# TIA.net
KiCad netlist of a schematic drawn in Altium Designer
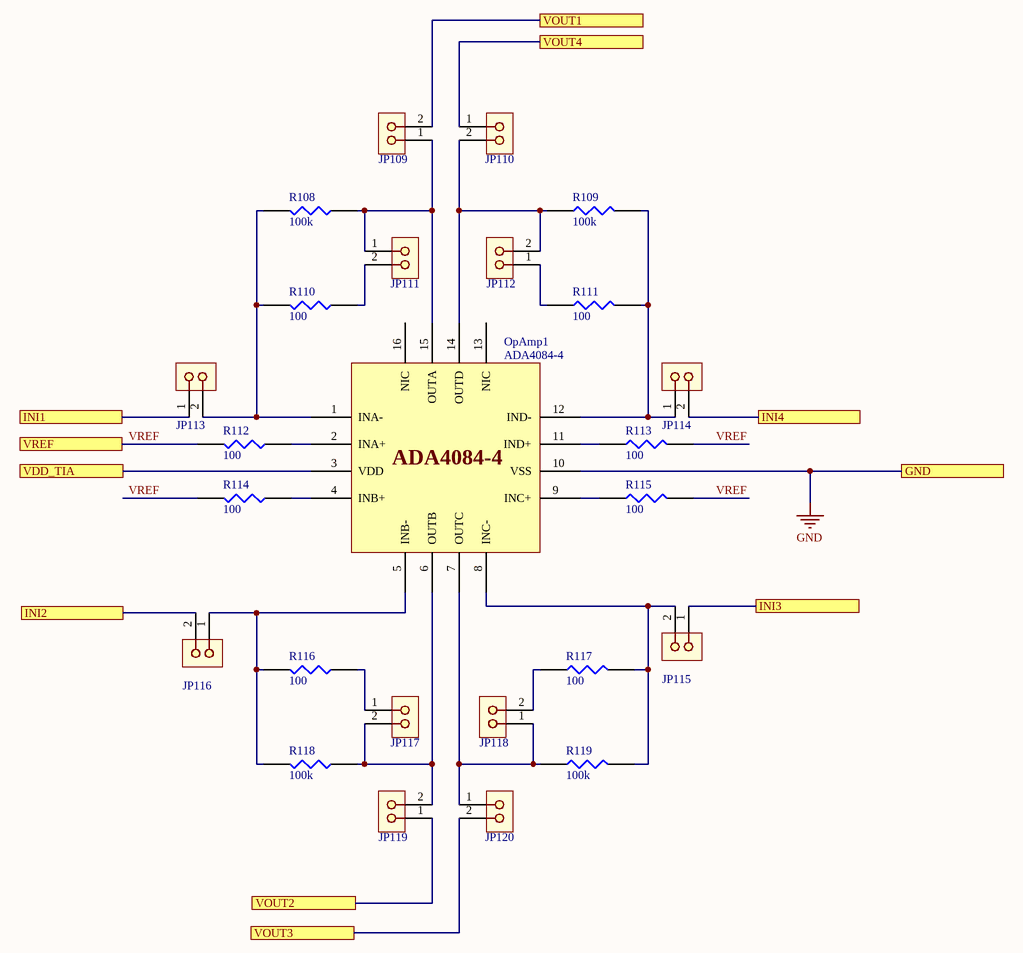
[diagram p0: TIA.SchDoc]

(export (version "E")
  (design (tool "Eeschema 10.0.6"))
  (components
    (comp (ref "JP109")
      (value "01x02")
      (footprint "01x02_0.1in_th_straight_b_nom")
      (description "01X02 generic terminal connector")
      (libsource (lib "") (part "01x02_2"))
    )
    (comp (ref "JP110")
      (value "01x02")
      (footprint "01x02_0.1in_th_straight_b_nom")
      (description "01X02 generic terminal connector")
      (libsource (lib "") (part "01x02_1"))
    )
    (comp (ref "JP111")
      (value "01x02")
      (footprint "01x02_0.1in_th_straight_b_nom")
      (description "01X02 generic terminal connector")
      (libsource (lib "") (part "01x02_1"))
    )
    (comp (ref "JP112")
      (value "01x02")
      (footprint "01x02_0.1in_th_straight_b_nom")
      (description "01X02 generic terminal connector")
      (libsource (lib "") (part "01x02_2"))
    )
    (comp (ref "JP113")
      (value "01x02")
      (footprint "01x02_0.1in_th_straight_b_nom")
      (description "01X02 generic terminal connector")
      (libsource (lib "") (part "01x02_3"))
    )
    (comp (ref "JP114")
      (value "01x02")
      (footprint "01x02_0.1in_th_straight_b_nom")
      (description "01X02 generic terminal connector")
      (libsource (lib "") (part "01x02_3"))
    )
    (comp (ref "JP115")
      (value "01x02")
      (footprint "01x02_0.1in_th_straight_b_nom")
      (description "01X02 generic terminal connector")
      (libsource (lib "Chip1_TestBoard") (part "01x02"))
    )
    (comp (ref "JP116")
      (value "01x02")
      (footprint "01x02_0.1in_th_straight_b_nom")
      (description "01X02 generic terminal connector")
      (libsource (lib "Chip1_TestBoard") (part "01x02"))
    )
    (comp (ref "JP117")
      (value "01x02")
      (footprint "01x02_0.1in_th_straight_b_nom")
      (description "01X02 generic terminal connector")
      (libsource (lib "") (part "01x02_1"))
    )
    (comp (ref "JP118")
      (value "01x02")
      (footprint "01x02_0.1in_th_straight_b_nom")
      (description "01X02 generic terminal connector")
      (libsource (lib "") (part "01x02_2"))
    )
    (comp (ref "JP119")
      (value "01x02")
      (footprint "01x02_0.1in_th_straight_b_nom")
      (description "01X02 generic terminal connector")
      (libsource (lib "") (part "01x02_2"))
    )
    (comp (ref "JP120")
      (value "01x02")
      (footprint "01x02_0.1in_th_straight_b_nom")
      (description "01X02 generic terminal connector")
      (libsource (lib "") (part "01x02_1"))
    )
    (comp (ref "OpAmp1")
      (value "ADA4084-4")
      (footprint "ADA4084-4")
      (description "Quad Ultra-Precision Op Amps")
      (libsource (lib "ICXTRAP1") (part "ADA4084-4"))
    )
    (comp (ref "R108")
      (value "100k")
      (footprint "R0805")
      (libsource (lib "Chip1_TestBoard") (part "Res 100k"))
    )
    (comp (ref "R109")
      (value "100k")
      (footprint "R0805")
      (libsource (lib "Chip1_TestBoard") (part "Res 100k"))
    )
    (comp (ref "R110") (value "100") (footprint "R0805") (libsource (lib "Chip1_TestBoard") (part "Res 100")))
    (comp (ref "R111") (value "100") (footprint "R0805") (libsource (lib "Chip1_TestBoard") (part "Res 100")))
    (comp (ref "R112") (value "100") (footprint "R0805") (libsource (lib "Chip1_TestBoard") (part "Res 100")))
    (comp (ref "R113") (value "100") (footprint "R0805") (libsource (lib "Chip1_TestBoard") (part "Res 100")))
    (comp (ref "R114") (value "100") (footprint "R0805") (libsource (lib "Chip1_TestBoard") (part "Res 100")))
    (comp (ref "R115") (value "100") (footprint "R0805") (libsource (lib "Chip1_TestBoard") (part "Res 100")))
    (comp (ref "R116") (value "100") (footprint "R0805") (libsource (lib "Chip1_TestBoard") (part "Res 100")))
    (comp (ref "R117") (value "100") (footprint "R0805") (libsource (lib "Chip1_TestBoard") (part "Res 100")))
    (comp (ref "R118")
      (value "100k")
      (footprint "R0805")
      (libsource (lib "Chip1_TestBoard") (part "Res 100k"))
    )
    (comp (ref "R119")
      (value "100k")
      (footprint "R0805")
      (libsource (lib "Chip1_TestBoard") (part "Res 100k"))
    )
  )
  (nets
    (net (code "1") (name "/INI1") (class "Default")
      (node (ref "JP113") (pin "1") (pinfunction "1_1") (pintype "passive"))
    )
    (net (code "2") (name "/INI2") (class "Default")
      (node (ref "JP116") (pin "2") (pinfunction "2_2") (pintype "passive"))
    )
    (net (code "3") (name "/INI3") (class "Default")
      (node (ref "JP115") (pin "1") (pinfunction "1_1") (pintype "passive"))
    )
    (net (code "4") (name "/INI4") (class "Default")
      (node (ref "JP114") (pin "2") (pinfunction "2_2") (pintype "passive"))
    )
    (net (code "5") (name "/VDD_TIA") (class "Default")
      (node (ref "OpAmp1") (pin "3") (pinfunction "VDD_3") (pintype "passive"))
    )
    (net (code "6") (name "/VOUT1") (class "Default")
      (node (ref "JP109") (pin "2") (pinfunction "2_2") (pintype "passive"))
    )
    (net (code "7") (name "/VOUT2") (class "Default")
      (node (ref "JP119") (pin "1") (pinfunction "1_1") (pintype "passive"))
    )
    (net (code "8") (name "/VOUT3") (class "Default")
      (node (ref "JP120") (pin "2") (pinfunction "2_2") (pintype "passive"))
    )
    (net (code "9") (name "/VOUT4") (class "Default")
      (node (ref "JP110") (pin "1") (pinfunction "1_1") (pintype "passive"))
    )
    (net (code "10") (name "/VREF") (class "Default")
      (node (ref "R112") (pin "2") (pinfunction "2_2") (pintype "passive"))
      (node (ref "R113") (pin "2") (pinfunction "2_2") (pintype "passive"))
      (node (ref "R114") (pin "2") (pinfunction "2_2") (pintype "passive"))
      (node (ref "R115") (pin "2") (pinfunction "2_2") (pintype "passive"))
    )
    (net (code "11") (name "GND") (class "Default")
      (node (ref "OpAmp1") (pin "10") (pinfunction "VSS_10") (pintype "passive"))
    )
    (net (code "12") (name "Net-(JP111-Pad2)") (class "Default")
      (node (ref "JP111") (pin "2") (pinfunction "2_2") (pintype "passive"))
      (node (ref "R110") (pin "1") (pinfunction "1_1") (pintype "passive"))
    )
    (net (code "13") (name "Net-(JP112-Pad1)") (class "Default")
      (node (ref "JP112") (pin "1") (pinfunction "1_1") (pintype "passive"))
      (node (ref "R111") (pin "1") (pinfunction "1_1") (pintype "passive"))
    )
    (net (code "14") (name "Net-(JP117-Pad1)") (class "Default")
      (node (ref "JP117") (pin "1") (pinfunction "1_1") (pintype "passive"))
      (node (ref "R116") (pin "1") (pinfunction "1_1") (pintype "passive"))
    )
    (net (code "15") (name "Net-(JP118-Pad2)") (class "Default")
      (node (ref "JP118") (pin "2") (pinfunction "2_2") (pintype "passive"))
      (node (ref "R117") (pin "1") (pinfunction "1_1") (pintype "passive"))
    )
    (net (code "16") (name "Net-(OpAmp1-INA+)") (class "Default")
      (node (ref "OpAmp1") (pin "2") (pinfunction "INA+_2") (pintype "passive"))
      (node (ref "R112") (pin "1") (pinfunction "1_1") (pintype "passive"))
    )
    (net (code "17") (name "Net-(OpAmp1-INA-)") (class "Default")
      (node (ref "JP113") (pin "2") (pinfunction "2_2") (pintype "passive"))
      (node (ref "OpAmp1") (pin "1") (pinfunction "INA-_1") (pintype "passive"))
      (node (ref "R108") (pin "2") (pinfunction "2_2") (pintype "passive"))
      (node (ref "R110") (pin "2") (pinfunction "2_2") (pintype "passive"))
    )
    (net (code "18") (name "Net-(OpAmp1-INB+)") (class "Default")
      (node (ref "OpAmp1") (pin "4") (pinfunction "INB+_4") (pintype "passive"))
      (node (ref "R114") (pin "1") (pinfunction "1_1") (pintype "passive"))
    )
    (net (code "19") (name "Net-(OpAmp1-INB-)") (class "Default")
      (node (ref "JP116") (pin "1") (pinfunction "1_1") (pintype "passive"))
      (node (ref "OpAmp1") (pin "5") (pinfunction "INB-_5") (pintype "passive"))
      (node (ref "R116") (pin "2") (pinfunction "2_2") (pintype "passive"))
      (node (ref "R118") (pin "2") (pinfunction "2_2") (pintype "passive"))
    )
    (net (code "20") (name "Net-(OpAmp1-INC+)") (class "Default")
      (node (ref "OpAmp1") (pin "9") (pinfunction "INC+_9") (pintype "passive"))
      (node (ref "R115") (pin "1") (pinfunction "1_1") (pintype "passive"))
    )
    (net (code "21") (name "Net-(OpAmp1-INC-)") (class "Default")
      (node (ref "JP115") (pin "2") (pinfunction "2_2") (pintype "passive"))
      (node (ref "OpAmp1") (pin "8") (pinfunction "INC-_8") (pintype "passive"))
      (node (ref "R117") (pin "2") (pinfunction "2_2") (pintype "passive"))
      (node (ref "R119") (pin "2") (pinfunction "2_2") (pintype "passive"))
    )
    (net (code "22") (name "Net-(OpAmp1-IND+)") (class "Default")
      (node (ref "OpAmp1") (pin "11") (pinfunction "IND+_11") (pintype "passive"))
      (node (ref "R113") (pin "1") (pinfunction "1_1") (pintype "passive"))
    )
    (net (code "23") (name "Net-(OpAmp1-IND-)") (class "Default")
      (node (ref "JP114") (pin "1") (pinfunction "1_1") (pintype "passive"))
      (node (ref "OpAmp1") (pin "12") (pinfunction "IND-_12") (pintype "passive"))
      (node (ref "R109") (pin "2") (pinfunction "2_2") (pintype "passive"))
      (node (ref "R111") (pin "2") (pinfunction "2_2") (pintype "passive"))
    )
    (net (code "24") (name "Net-(OpAmp1-OUTA)") (class "Default")
      (node (ref "JP109") (pin "1") (pinfunction "1_1") (pintype "passive"))
      (node (ref "JP111") (pin "1") (pinfunction "1_1") (pintype "passive"))
      (node (ref "OpAmp1") (pin "15") (pinfunction "OUTA_15") (pintype "passive"))
      (node (ref "R108") (pin "1") (pinfunction "1_1") (pintype "passive"))
    )
    (net (code "25") (name "Net-(OpAmp1-OUTB)") (class "Default")
      (node (ref "JP117") (pin "2") (pinfunction "2_2") (pintype "passive"))
      (node (ref "JP119") (pin "2") (pinfunction "2_2") (pintype "passive"))
      (node (ref "OpAmp1") (pin "6") (pinfunction "OUTB_6") (pintype "passive"))
      (node (ref "R118") (pin "1") (pinfunction "1_1") (pintype "passive"))
    )
    (net (code "26") (name "Net-(OpAmp1-OUTC)") (class "Default")
      (node (ref "JP118") (pin "1") (pinfunction "1_1") (pintype "passive"))
      (node (ref "JP120") (pin "1") (pinfunction "1_1") (pintype "passive"))
      (node (ref "OpAmp1") (pin "7") (pinfunction "OUTC_7") (pintype "passive"))
      (node (ref "R119") (pin "1") (pinfunction "1_1") (pintype "passive"))
    )
    (net (code "27") (name "Net-(OpAmp1-OUTD)") (class "Default")
      (node (ref "JP110") (pin "2") (pinfunction "2_2") (pintype "passive"))
      (node (ref "JP112") (pin "2") (pinfunction "2_2") (pintype "passive"))
      (node (ref "OpAmp1") (pin "14") (pinfunction "OUTD_14") (pintype "passive"))
      (node (ref "R109") (pin "1") (pinfunction "1_1") (pintype "passive"))
    )
    (net (code "28") (name "unconnected-(OpAmp1-NIC-Pad13)") (class "Default")
      (node (ref "OpAmp1") (pin "13") (pinfunction "NIC_13") (pintype "passive"))
    )
    (net (code "29") (name "unconnected-(OpAmp1-NIC-Pad16)") (class "Default")
      (node (ref "OpAmp1") (pin "16") (pinfunction "NIC_16") (pintype "passive"))
    )
  )
)
